# untitled.net
KiCad netlist of a schematic drawn in EAGLE
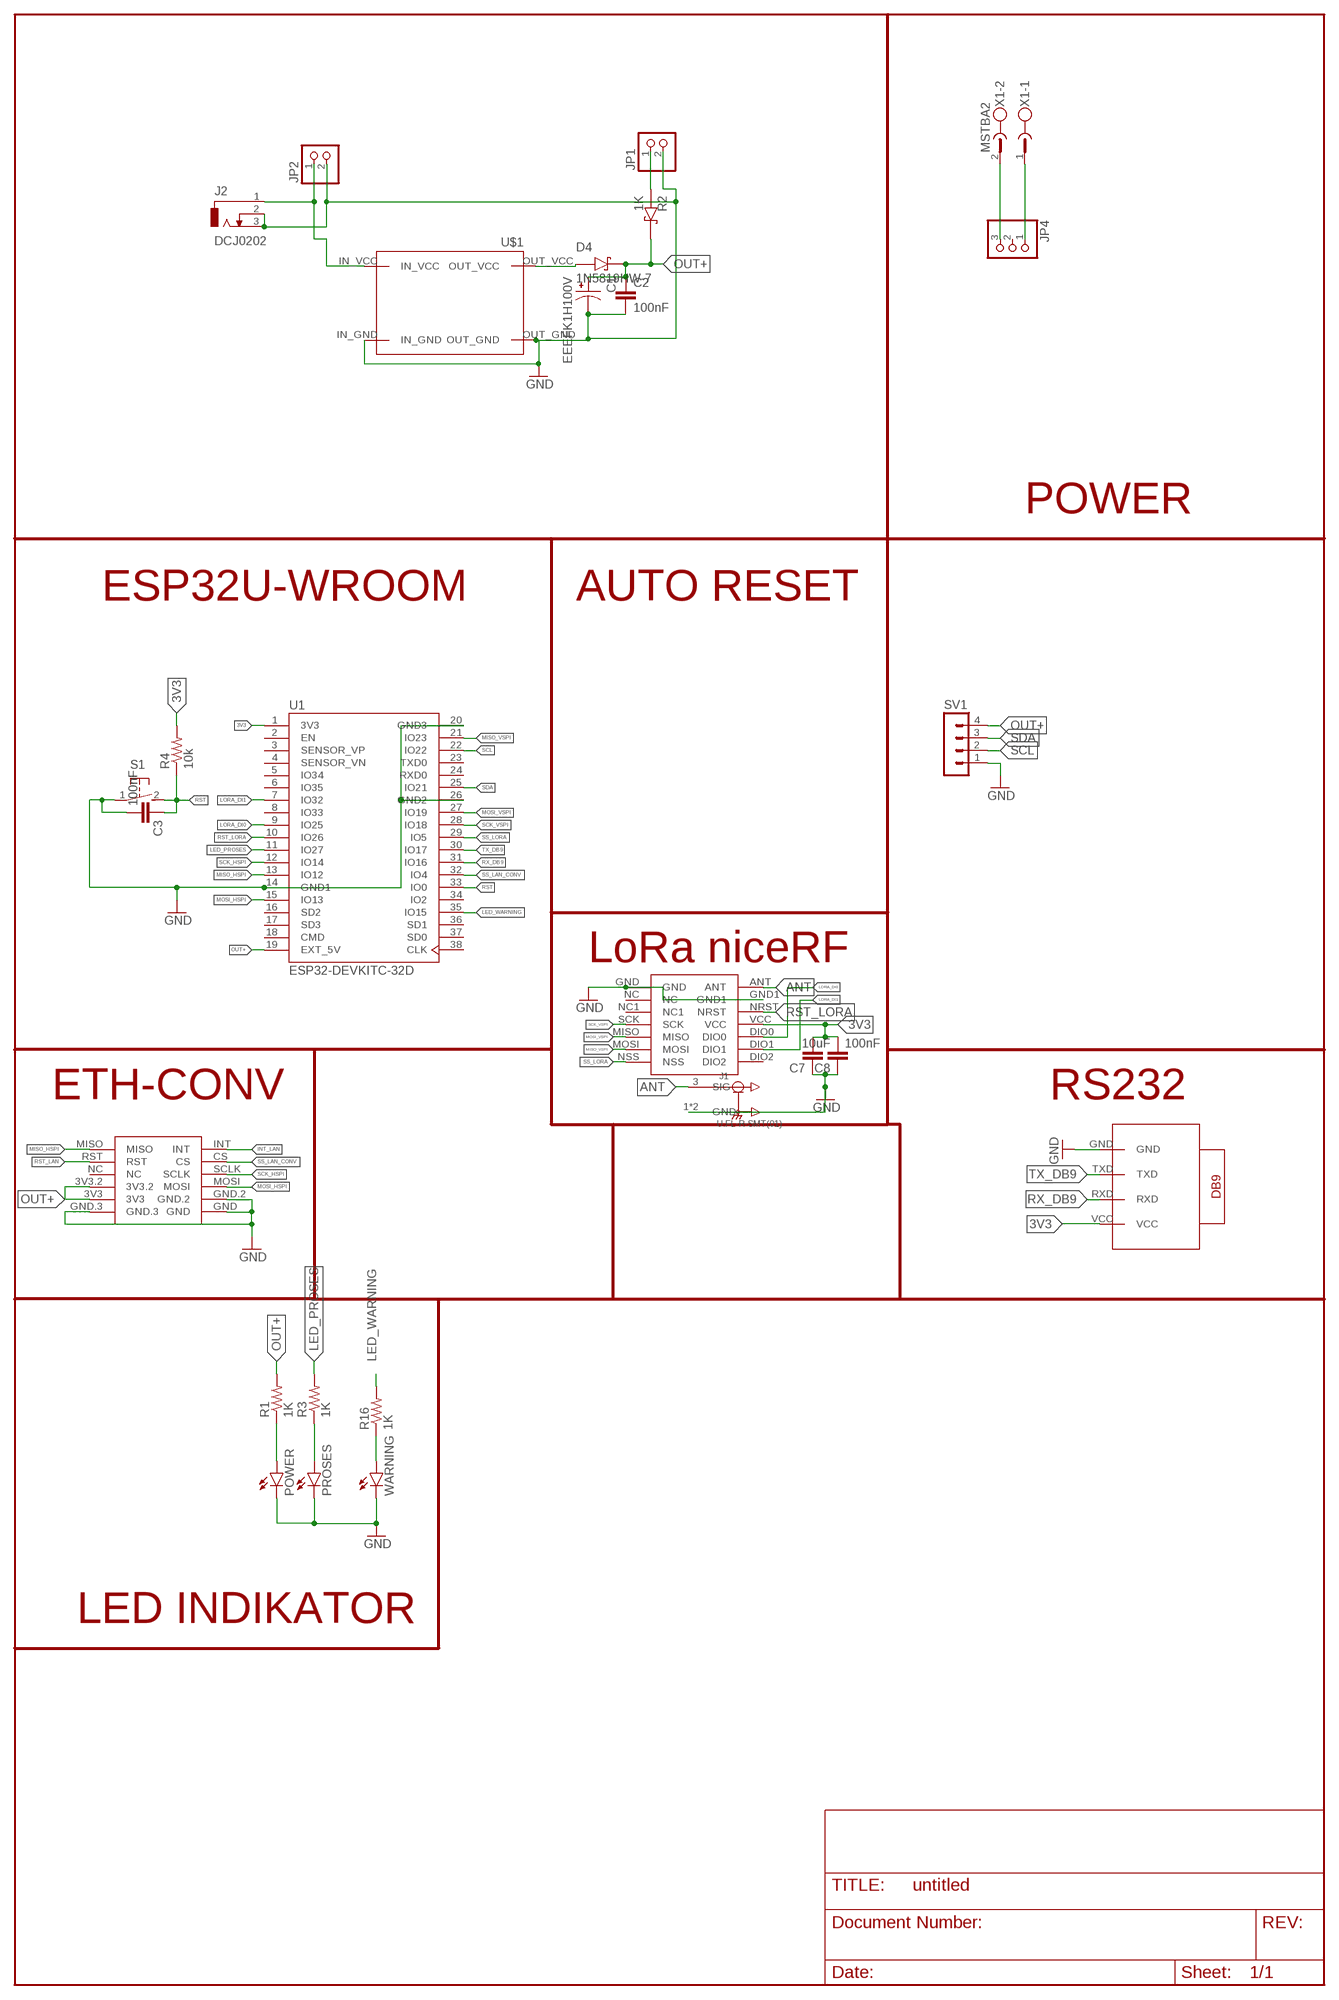
[diagram p0: schematic, sheet 1]

(export (version "E")
  (design (tool "Eeschema 10.0.6"))
  (components
    (comp (ref "C1")
      (value "EEEFK1H100V")
      (footprint "eagle-import:CAP_EEEFK1H100V")
      (fields (field (name "MF") "Panasonic"))
      (libsource (lib "eagle-import") (part "EEEFK1H100V"))
    )
    (comp (ref "C2")
      (value "100nF")
      (footprint "eagle-import:C0805K")
      (libsource (lib "eagle-import") (part "C-EUC0805K"))
    )
    (comp (ref "C3")
      (value "100nF")
      (footprint "eagle-import:C0805K")
      (libsource (lib "eagle-import") (part "C-EUC0805K"))
    )
    (comp (ref "C7")
      (value "10uF")
      (footprint "eagle-import:C0805K")
      (libsource (lib "eagle-import") (part "C-EUC0805K"))
    )
    (comp (ref "C8")
      (value "100nF")
      (footprint "eagle-import:C0805K")
      (libsource (lib "eagle-import") (part "C-EUC0805K"))
    )
    (comp (ref "D4")
      (value "1N5819HW-7")
      (footprint "eagle-import:SOD3715X145N")
      (fields (field (name "MF") "Diodes Inc."))
      (libsource (lib "eagle-import") (part "1N5819HW-7"))
    )
    (comp (ref "J1")
      (value "U.FL-R-SMT(01)")
      (footprint "eagle-import:HRS_U.FL-R-SMT(01)")
      (fields (field (name "MF") "Hirose"))
      (libsource (lib "eagle-import") (part "U.FL-R-SMT(01)"))
    )
    (comp (ref "J2")
      (value "DCJ0202")
      (footprint "eagle-import:DCJ0202")
      (libsource (lib "eagle-import") (part "DCJ0202"))
    )
    (comp (ref "JP1")
      (value "PINHD-1X2")
      (footprint "eagle-import:1X02")
      (libsource (lib "eagle-import") (part "PINHD-1X2"))
    )
    (comp (ref "JP2")
      (value "PINHD-1X2")
      (footprint "eagle-import:1X02")
      (libsource (lib "eagle-import") (part "PINHD-1X2"))
    )
    (comp (ref "JP4")
      (value "PINHD-1X3")
      (footprint "eagle-import:1X03")
      (libsource (lib "eagle-import") (part "PINHD-1X3"))
    )
    (comp (ref "LORA-NICERF-V1")
      (value "LORA-NICERF-V2")
      (footprint "eagle-import:LORA-NICERF-V2")
      (libsource (lib "eagle-import") (part "LORA-NICERF-V2"))
    )
    (comp (ref "POWER")
      (value "TLLR4400")
      (footprint "eagle-import:LED3MM")
      (fields (field (name "MF") "VISHAY SEMICONDUCTOR"))
      (libsource (lib "eagle-import") (part "TLLR4400"))
    )
    (comp (ref "PROSES")
      (value "TLLR4400")
      (footprint "eagle-import:LED3MM")
      (fields (field (name "MF") "VISHAY SEMICONDUCTOR"))
      (libsource (lib "eagle-import") (part "TLLR4400"))
    )
    (comp (ref "R1")
      (value "1K")
      (footprint "eagle-import:M0805")
      (libsource (lib "eagle-import") (part "R-US_M0805"))
    )
    (comp (ref "R2")
      (value "1K")
      (footprint "eagle-import:SOD3715X145N")
      (fields (field (name "MF") "Diodes Inc.") (field (name "MP") "1N5819HW-7"))
      (libsource (lib "eagle-import") (part "1N5819HW-7"))
    )
    (comp (ref "R3")
      (value "1K")
      (footprint "eagle-import:M0805")
      (libsource (lib "eagle-import") (part "R-US_M0805"))
    )
    (comp (ref "R4")
      (value "10k")
      (footprint "eagle-import:M0805")
      (libsource (lib "eagle-import") (part "R-US_M0805"))
    )
    (comp (ref "R16")
      (value "1K")
      (footprint "eagle-import:M0805")
      (libsource (lib "eagle-import") (part "R-US_M0805"))
    )
    (comp (ref "S1")
      (value "31-XX")
      (footprint "eagle-import:B3F-31XX")
      (fields (field (name "MPN") "B3F-3100"))
      (libsource (lib "eagle-import") (part "31-XX"))
    )
    (comp (ref "SV1")
      (value "MA04-1")
      (footprint "eagle-import:MA04-1")
      (libsource (lib "eagle-import") (part "MA04-1"))
    )
    (comp (ref "U$1")
      (value "STEPDOWN_SY8205")
      (footprint "eagle-import:STEPDOWN_SY8205")
      (libsource (lib "eagle-import") (part "STEPDOWN_SY8205"))
    )
    (comp (ref "U$3")
      (value "MINI_W5500")
      (footprint "eagle-import:MINI_W5500")
      (libsource (lib "eagle-import") (part "MINI_W5500"))
    )
    (comp (ref "U$5")
      (value "RS232-BREAKOUTBREAKOUT")
      (footprint "eagle-import:RS232-BREAKOUT")
      (libsource (lib "eagle-import") (part "RS232-BREAKOUTBREAKOUT"))
    )
    (comp (ref "U1")
      (value "ESP32-DEVKITC-32D")
      (footprint "eagle-import:MODULE_ESP32-DEVKITC-32D")
      (fields (field (name "MF") "Espressif Systems"))
      (libsource (lib "eagle-import") (part "ESP32-DEVKITC-32D"))
    )
    (comp (ref "WARNING")
      (value "TLLR4400")
      (footprint "eagle-import:LED3MM")
      (fields (field (name "MF") "VISHAY SEMICONDUCTOR"))
      (libsource (lib "eagle-import") (part "TLLR4400"))
    )
    (comp (ref "X1")
      (value "MSTBA2")
      (footprint "eagle-import:MSTBA2")
      (fields (field (name "MF") "FARNELL") (field (name "MPN") "1757242"))
      (libsource (lib "eagle-import") (part "MSTBA2"))
    )
  )
  (nets
    (net (code "1") (name "3V3") (class "Default")
      (node (ref "C7") (pin "2") (pinfunction "2_2") (pintype "passive"))
      (node (ref "C8") (pin "2") (pinfunction "2_2") (pintype "passive"))
      (node (ref "LORA-NICERF-V1") (pin "VCC") (pinfunction "VCC_VCC") (pintype "bidirectional"))
      (node (ref "R4") (pin "2") (pinfunction "2_2") (pintype "passive"))
      (node (ref "U$5") (pin "VCC") (pinfunction "VCC_VCC") (pintype "bidirectional"))
      (node (ref "U1") (pin "1") (pinfunction "3V3_1") (pintype "power_in"))
    )
    (net (code "2") (name "ANT") (class "Default")
      (node (ref "J1") (pin "3") (pinfunction "SIG_3") (pintype "passive"))
      (node (ref "LORA-NICERF-V1") (pin "ANT") (pinfunction "ANT_ANT") (pintype "bidirectional"))
    )
    (net (code "3") (name "GND") (class "Default")
      (node (ref "C1") (pin "2") (pinfunction "2_2") (pintype "passive"))
      (node (ref "C2") (pin "2") (pinfunction "2_2") (pintype "passive"))
      (node (ref "C3") (pin "2") (pinfunction "2_2") (pintype "passive"))
      (node (ref "C7") (pin "1") (pinfunction "1_1") (pintype "passive"))
      (node (ref "C8") (pin "1") (pinfunction "1_1") (pintype "passive"))
      (node (ref "J1") (pin "1") (pinfunction "GND_1") (pintype "passive"))
      (node (ref "J1") (pin "2") (pinfunction "GND_2") (pintype "passive"))
      (node (ref "J2") (pin "2") (pinfunction "2_2") (pintype "passive"))
      (node (ref "J2") (pin "3") (pinfunction "3_3") (pintype "passive"))
      (node (ref "JP1") (pin "2") (pinfunction "2_2") (pintype "passive"))
      (node (ref "JP2") (pin "2") (pinfunction "2_2") (pintype "passive"))
      (node (ref "LORA-NICERF-V1") (pin "GND") (pinfunction "GND_GND") (pintype "bidirectional"))
      (node (ref "LORA-NICERF-V1") (pin "GND1") (pinfunction "GND1_GND1") (pintype "bidirectional"))
      (node (ref "POWER") (pin "K") (pinfunction "C_K") (pintype "passive"))
      (node (ref "PROSES") (pin "K") (pinfunction "C_K") (pintype "passive"))
      (node (ref "S1") (pin "1") (pinfunction "P_1") (pintype "passive"))
      (node (ref "SV1") (pin "1") (pinfunction "1_1") (pintype "passive"))
      (node (ref "U$1") (pin "IN_GND") (pinfunction "IN_GND_IN_GND") (pintype "bidirectional"))
      (node (ref "U$1") (pin "OUT_GND") (pinfunction "OUT_GND_OUT_GND") (pintype "bidirectional"))
      (node (ref "U$3") (pin "GND") (pinfunction "GND_GND") (pintype "bidirectional"))
      (node (ref "U$3") (pin "GND.2") (pinfunction "GND.2_GND.2") (pintype "bidirectional"))
      (node (ref "U$3") (pin "GND.3") (pinfunction "GND.3_GND.3") (pintype "bidirectional"))
      (node (ref "U$5") (pin "GND") (pinfunction "GND_GND") (pintype "bidirectional"))
      (node (ref "U1") (pin "14") (pinfunction "GND1_14") (pintype "power_in"))
      (node (ref "U1") (pin "20") (pinfunction "GND3_20") (pintype "power_in"))
      (node (ref "U1") (pin "26") (pinfunction "GND2_26") (pintype "power_in"))
      (node (ref "WARNING") (pin "K") (pinfunction "C_K") (pintype "passive"))
    )
    (net (code "4") (name "INT_LAN") (class "Default")
      (node (ref "U$3") (pin "INT") (pinfunction "INT_INT") (pintype "bidirectional"))
    )
    (net (code "5") (name "LED_PROSES") (class "Default")
      (node (ref "R3") (pin "2") (pinfunction "2_2") (pintype "passive"))
      (node (ref "U1") (pin "11") (pinfunction "IO27_11") (pintype "bidirectional"))
    )
    (net (code "6") (name "LED_WARNING") (class "Default")
      (node (ref "R16") (pin "2") (pinfunction "2_2") (pintype "passive"))
      (node (ref "U1") (pin "35") (pinfunction "IO15_35") (pintype "bidirectional"))
    )
    (net (code "7") (name "LORA_DI0") (class "Default")
      (node (ref "LORA-NICERF-V1") (pin "DIO0") (pinfunction "DIO0_DIO0") (pintype "bidirectional"))
      (node (ref "U1") (pin "9") (pinfunction "IO25_9") (pintype "bidirectional"))
    )
    (net (code "8") (name "LORA_DI1") (class "Default")
      (node (ref "LORA-NICERF-V1") (pin "DIO1") (pinfunction "DIO1_DIO1") (pintype "bidirectional"))
      (node (ref "U1") (pin "7") (pinfunction "IO32_7") (pintype "bidirectional"))
    )
    (net (code "9") (name "MISO_HSPI") (class "Default")
      (node (ref "U$3") (pin "MISO") (pinfunction "MISO_MISO") (pintype "bidirectional"))
      (node (ref "U1") (pin "13") (pinfunction "IO12_13") (pintype "bidirectional"))
    )
    (net (code "10") (name "MISO_VSPI") (class "Default")
      (node (ref "LORA-NICERF-V1") (pin "MOSI") (pinfunction "MOSI_MOSI") (pintype "bidirectional"))
      (node (ref "U1") (pin "21") (pinfunction "IO23_21") (pintype "bidirectional"))
    )
    (net (code "11") (name "MOSI_HSPI") (class "Default")
      (node (ref "U$3") (pin "MOSI") (pinfunction "MOSI_MOSI") (pintype "bidirectional"))
      (node (ref "U1") (pin "15") (pinfunction "IO13_15") (pintype "bidirectional"))
    )
    (net (code "12") (name "MOSI_VSPI") (class "Default")
      (node (ref "LORA-NICERF-V1") (pin "MISO") (pinfunction "MISO_MISO") (pintype "bidirectional"))
      (node (ref "U1") (pin "27") (pinfunction "IO19_27") (pintype "bidirectional"))
    )
    (net (code "13") (name "Net-(D4-PadA)") (class "Default")
      (node (ref "D4") (pin "A") (pinfunction "A_A") (pintype "passive"))
      (node (ref "U$1") (pin "OUT_VCC") (pinfunction "OUT_VCC_OUT_VCC") (pintype "bidirectional"))
    )
    (net (code "14") (name "Net-(J2-Pad1)") (class "Default")
      (node (ref "J2") (pin "1") (pinfunction "1_1") (pintype "passive"))
      (node (ref "JP2") (pin "1") (pinfunction "1_1") (pintype "passive"))
      (node (ref "U$1") (pin "IN_VCC") (pinfunction "IN_VCC_IN_VCC") (pintype "bidirectional"))
    )
    (net (code "15") (name "Net-(JP1-Pad1)") (class "Default")
      (node (ref "JP1") (pin "1") (pinfunction "1_1") (pintype "passive"))
      (node (ref "R2") (pin "A") (pinfunction "A_A") (pintype "passive"))
    )
    (net (code "16") (name "Net-(JP4-Pad1)") (class "Default")
      (node (ref "JP4") (pin "1") (pinfunction "1_1") (pintype "passive"))
      (node (ref "X1") (pin "1") (pinfunction "1_1") (pintype "passive"))
    )
    (net (code "17") (name "Net-(POWER-PadA)") (class "Default")
      (node (ref "POWER") (pin "A") (pinfunction "A_A") (pintype "passive"))
      (node (ref "R1") (pin "1") (pinfunction "1_1") (pintype "passive"))
    )
    (net (code "18") (name "Net-(PROSES-PadA)") (class "Default")
      (node (ref "PROSES") (pin "A") (pinfunction "A_A") (pintype "passive"))
      (node (ref "R3") (pin "1") (pinfunction "1_1") (pintype "passive"))
    )
    (net (code "19") (name "Net-(R16-Pad1)") (class "Default")
      (node (ref "R16") (pin "1") (pinfunction "1_1") (pintype "passive"))
      (node (ref "WARNING") (pin "A") (pinfunction "A_A") (pintype "passive"))
    )
    (net (code "20") (name "Net-(X1B-1)") (class "Default")
      (node (ref "JP4") (pin "3") (pinfunction "3_3") (pintype "passive"))
      (node (ref "X1") (pin "2") (pinfunction "1_2") (pintype "passive"))
    )
    (net (code "21") (name "OUT+") (class "Default")
      (node (ref "C1") (pin "1") (pinfunction "1_1") (pintype "passive"))
      (node (ref "C2") (pin "1") (pinfunction "1_1") (pintype "passive"))
      (node (ref "D4") (pin "C") (pinfunction "K_C") (pintype "passive"))
      (node (ref "R1") (pin "2") (pinfunction "2_2") (pintype "passive"))
      (node (ref "R2") (pin "C") (pinfunction "K_C") (pintype "passive"))
      (node (ref "SV1") (pin "4") (pinfunction "4_4") (pintype "passive"))
      (node (ref "U$3") (pin "3V3") (pinfunction "3V3_3V3") (pintype "bidirectional"))
      (node (ref "U$3") (pin "3V3.2") (pinfunction "3V3.2_3V3.2") (pintype "bidirectional"))
      (node (ref "U1") (pin "19") (pinfunction "EXT_5V_19") (pintype "power_in"))
    )
    (net (code "22") (name "RST") (class "Default")
      (node (ref "C3") (pin "1") (pinfunction "1_1") (pintype "passive"))
      (node (ref "R4") (pin "1") (pinfunction "1_1") (pintype "passive"))
      (node (ref "S1") (pin "2") (pinfunction "S_2") (pintype "passive"))
      (node (ref "U1") (pin "33") (pinfunction "IO0_33") (pintype "bidirectional"))
    )
    (net (code "23") (name "RST_LAN") (class "Default")
      (node (ref "U$3") (pin "RST") (pinfunction "RST_RST") (pintype "bidirectional"))
    )
    (net (code "24") (name "RST_LORA") (class "Default")
      (node (ref "LORA-NICERF-V1") (pin "NRST") (pinfunction "NRST_NRST") (pintype "bidirectional"))
      (node (ref "U1") (pin "10") (pinfunction "IO26_10") (pintype "bidirectional"))
    )
    (net (code "25") (name "RX_DB9") (class "Default")
      (node (ref "U$5") (pin "RXD") (pinfunction "RXD_RXD") (pintype "bidirectional"))
      (node (ref "U1") (pin "31") (pinfunction "IO16_31") (pintype "bidirectional"))
    )
    (net (code "26") (name "SCK_HSPI") (class "Default")
      (node (ref "U$3") (pin "SCLK") (pinfunction "SCLK_SCLK") (pintype "bidirectional"))
      (node (ref "U1") (pin "12") (pinfunction "IO14_12") (pintype "bidirectional"))
    )
    (net (code "27") (name "SCK_VSPI") (class "Default")
      (node (ref "LORA-NICERF-V1") (pin "SCK") (pinfunction "SCK_SCK") (pintype "bidirectional"))
      (node (ref "U1") (pin "28") (pinfunction "IO18_28") (pintype "bidirectional"))
    )
    (net (code "28") (name "SCL") (class "Default")
      (node (ref "SV1") (pin "2") (pinfunction "2_2") (pintype "passive"))
      (node (ref "U1") (pin "22") (pinfunction "IO22_22") (pintype "bidirectional"))
    )
    (net (code "29") (name "SDA") (class "Default")
      (node (ref "SV1") (pin "3") (pinfunction "3_3") (pintype "passive"))
      (node (ref "U1") (pin "25") (pinfunction "IO21_25") (pintype "bidirectional"))
    )
    (net (code "30") (name "SS_LAN_CONV") (class "Default")
      (node (ref "U$3") (pin "CS") (pinfunction "CS_CS") (pintype "bidirectional"))
      (node (ref "U1") (pin "32") (pinfunction "IO4_32") (pintype "bidirectional"))
    )
    (net (code "31") (name "SS_LORA") (class "Default")
      (node (ref "LORA-NICERF-V1") (pin "NSS") (pinfunction "NSS_NSS") (pintype "bidirectional"))
      (node (ref "U1") (pin "29") (pinfunction "IO5_29") (pintype "bidirectional"))
    )
    (net (code "32") (name "TX_DB9") (class "Default")
      (node (ref "U$5") (pin "TXD") (pinfunction "TXD_TXD") (pintype "bidirectional"))
      (node (ref "U1") (pin "30") (pinfunction "IO17_30") (pintype "bidirectional"))
    )
    (net (code "33") (name "unconnected-(JP4-Pad2)") (class "Default")
      (node (ref "JP4") (pin "2") (pinfunction "2_2") (pintype "passive"))
    )
    (net (code "34") (name "unconnected-(LORA-NICERF-V1-PadDIO2)") (class "Default")
      (node (ref "LORA-NICERF-V1") (pin "DIO2") (pinfunction "DIO2_DIO2") (pintype "bidirectional"))
    )
    (net (code "35") (name "unconnected-(LORA-NICERF-V1-PadNC)") (class "Default")
      (node (ref "LORA-NICERF-V1") (pin "NC") (pinfunction "NC_NC") (pintype "bidirectional"))
    )
    (net (code "36") (name "unconnected-(LORA-NICERF-V1-PadNC1)") (class "Default")
      (node (ref "LORA-NICERF-V1") (pin "NC1") (pinfunction "NC1_NC1") (pintype "bidirectional"))
    )
    (net (code "37") (name "unconnected-(U$3-PadNC)") (class "Default")
      (node (ref "U$3") (pin "NC") (pinfunction "NC_NC") (pintype "bidirectional"))
    )
    (net (code "38") (name "unconnected-(U1-CLK-Pad38)") (class "Default")
      (node (ref "U1") (pin "38") (pinfunction "CLK_38") (pintype "input"))
    )
    (net (code "39") (name "unconnected-(U1-CMD-Pad18)") (class "Default")
      (node (ref "U1") (pin "18") (pinfunction "CMD_18") (pintype "bidirectional"))
    )
    (net (code "40") (name "unconnected-(U1-EN-Pad2)") (class "Default")
      (node (ref "U1") (pin "2") (pinfunction "EN_2") (pintype "input"))
    )
    (net (code "41") (name "unconnected-(U1-IO2-Pad34)") (class "Default")
      (node (ref "U1") (pin "34") (pinfunction "IO2_34") (pintype "bidirectional"))
    )
    (net (code "42") (name "unconnected-(U1-IO33-Pad8)") (class "Default")
      (node (ref "U1") (pin "8") (pinfunction "IO33_8") (pintype "bidirectional"))
    )
    (net (code "43") (name "unconnected-(U1-IO34-Pad5)") (class "Default")
      (node (ref "U1") (pin "5") (pinfunction "IO34_5") (pintype "bidirectional"))
    )
    (net (code "44") (name "unconnected-(U1-IO35-Pad6)") (class "Default")
      (node (ref "U1") (pin "6") (pinfunction "IO35_6") (pintype "bidirectional"))
    )
    (net (code "45") (name "unconnected-(U1-RXD0-Pad24)") (class "Default")
      (node (ref "U1") (pin "24") (pinfunction "RXD0_24") (pintype "input"))
    )
    (net (code "46") (name "unconnected-(U1-SD0-Pad37)") (class "Default")
      (node (ref "U1") (pin "37") (pinfunction "SD0_37") (pintype "bidirectional"))
    )
    (net (code "47") (name "unconnected-(U1-SD1-Pad36)") (class "Default")
      (node (ref "U1") (pin "36") (pinfunction "SD1_36") (pintype "bidirectional"))
    )
    (net (code "48") (name "unconnected-(U1-SD2-Pad16)") (class "Default")
      (node (ref "U1") (pin "16") (pinfunction "SD2_16") (pintype "bidirectional"))
    )
    (net (code "49") (name "unconnected-(U1-SD3-Pad17)") (class "Default")
      (node (ref "U1") (pin "17") (pinfunction "SD3_17") (pintype "bidirectional"))
    )
    (net (code "50") (name "unconnected-(U1-SENSOR_VN-Pad4)") (class "Default")
      (node (ref "U1") (pin "4") (pinfunction "SENSOR_VN_4") (pintype "input"))
    )
    (net (code "51") (name "unconnected-(U1-SENSOR_VP-Pad3)") (class "Default")
      (node (ref "U1") (pin "3") (pinfunction "SENSOR_VP_3") (pintype "input"))
    )
    (net (code "52") (name "unconnected-(U1-TXD0-Pad23)") (class "Default")
      (node (ref "U1") (pin "23") (pinfunction "TXD0_23") (pintype "output"))
    )
  )
)
